# LEDATTACK.net
KiCad netlist of a schematic drawn in EAGLE
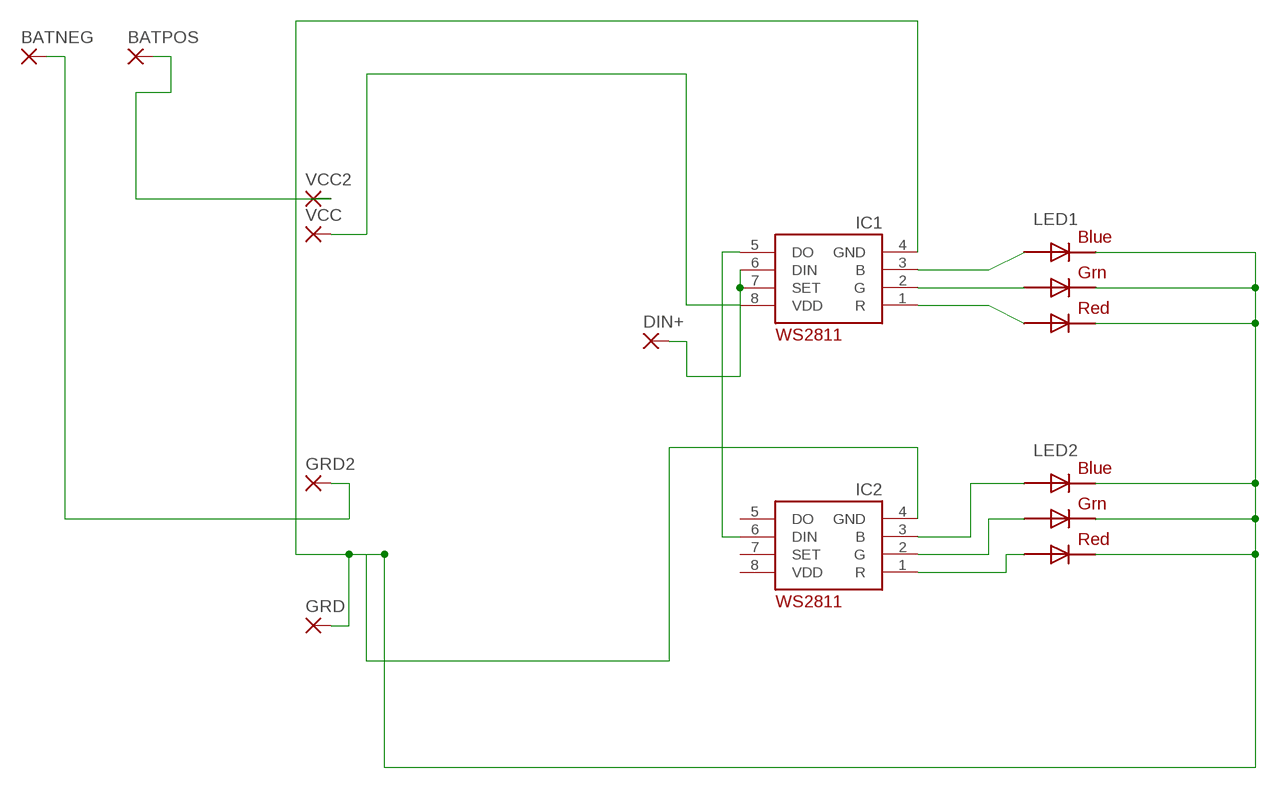
[diagram p0: schematic, sheet 1]

(export (version "E")
  (design (tool "Eeschema 10.0.6"))
  (components
    (comp (ref "BATNEG")
      (value "1,6/0,8")
      (footprint "eagle-import:1,6_0,8")
      (libsource (lib "eagle-import") (part "1,6/0,8"))
    )
    (comp (ref "BATPOS")
      (value "1,6/0,8")
      (footprint "eagle-import:1,6_0,8")
      (libsource (lib "eagle-import") (part "1,6/0,8"))
    )
    (comp (ref "DIN+")
      (value "1,6/0,8")
      (footprint "eagle-import:1,6_0,8")
      (libsource (lib "eagle-import") (part "1,6/0,8"))
    )
    (comp (ref "GRD")
      (value "1,6/0,8")
      (footprint "eagle-import:1,6_0,8")
      (libsource (lib "eagle-import") (part "1,6/0,8"))
    )
    (comp (ref "GRD2")
      (value "1,6/0,8")
      (footprint "eagle-import:1,6_0,8")
      (libsource (lib "eagle-import") (part "1,6/0,8"))
    )
    (comp (ref "IC1")
      (value "WS2811-SOP8")
      (footprint "eagle-import:SO08-SKINNYPADS")
      (libsource (lib "eagle-import") (part "WS2811-SOP8"))
    )
    (comp (ref "IC2")
      (value "WS2811-SOP8")
      (footprint "eagle-import:SO08-SKINNYPADS")
      (libsource (lib "eagle-import") (part "WS2811-SOP8"))
    )
    (comp (ref "LED1")
      (value "RGBLED5050")
      (footprint "eagle-import:RGBLED5050")
      (libsource (lib "eagle-import") (part "RGBLED5050"))
    )
    (comp (ref "LED2")
      (value "RGBLED5050")
      (footprint "eagle-import:RGBLED5050")
      (libsource (lib "eagle-import") (part "RGBLED5050"))
    )
    (comp (ref "VCC")
      (value "1,6/0,8")
      (footprint "eagle-import:1,6_0,8")
      (libsource (lib "eagle-import") (part "1,6/0,8"))
    )
    (comp (ref "VCC2")
      (value "1,6/0,8")
      (footprint "eagle-import:1,6_0,8")
      (libsource (lib "eagle-import") (part "1,6/0,8"))
    )
  )
  (nets
    (net (code "1") (name "/VDD") (class "Default")
      (node (ref "IC2") (pin "8") (pinfunction "VDD_8") (pintype "power_in"))
    )
    (net (code "2") (name "Net-(BATNEG-P)") (class "Default")
      (node (ref "BATNEG") (pin "1") (pinfunction "P_1") (pintype "passive"))
      (node (ref "GRD2") (pin "1") (pinfunction "P_1") (pintype "passive"))
    )
    (net (code "3") (name "Net-(BATPOS-P)") (class "Default")
      (node (ref "BATPOS") (pin "1") (pinfunction "P_1") (pintype "passive"))
      (node (ref "VCC2") (pin "1") (pinfunction "P_1") (pintype "passive"))
    )
    (net (code "4") (name "Net-(DIN+-P)") (class "Default")
      (node (ref "DIN+") (pin "1") (pinfunction "P_1") (pintype "passive"))
      (node (ref "IC1") (pin "6") (pinfunction "DIN_6") (pintype "input"))
      (node (ref "IC1") (pin "7") (pinfunction "SET_7") (pintype "input"))
    )
    (net (code "5") (name "Net-(GRD-P)") (class "Default")
      (node (ref "GRD") (pin "1") (pinfunction "P_1") (pintype "passive"))
      (node (ref "IC1") (pin "4") (pinfunction "GND_4") (pintype "power_in"))
      (node (ref "IC2") (pin "4") (pinfunction "GND_4") (pintype "power_in"))
      (node (ref "LED1") (pin "4") (pinfunction "BLUE_C_4") (pintype "bidirectional"))
      (node (ref "LED1") (pin "5") (pinfunction "RED_C_5") (pintype "bidirectional"))
      (node (ref "LED1") (pin "6") (pinfunction "GREEN_C_6") (pintype "bidirectional"))
      (node (ref "LED2") (pin "4") (pinfunction "BLUE_C_4") (pintype "bidirectional"))
      (node (ref "LED2") (pin "5") (pinfunction "RED_C_5") (pintype "bidirectional"))
      (node (ref "LED2") (pin "6") (pinfunction "GREEN_C_6") (pintype "bidirectional"))
    )
    (net (code "6") (name "Net-(IC1-B)") (class "Default")
      (node (ref "IC1") (pin "3") (pinfunction "B_3") (pintype "open_collector"))
      (node (ref "LED1") (pin "3") (pinfunction "BLUE_A_3") (pintype "bidirectional"))
    )
    (net (code "7") (name "Net-(IC1-DO)") (class "Default")
      (node (ref "IC1") (pin "5") (pinfunction "DO_5") (pintype "output"))
      (node (ref "IC2") (pin "6") (pinfunction "DIN_6") (pintype "input"))
    )
    (net (code "8") (name "Net-(IC1-G)") (class "Default")
      (node (ref "IC1") (pin "2") (pinfunction "G_2") (pintype "open_collector"))
      (node (ref "LED1") (pin "1") (pinfunction "GREEN_A_1") (pintype "bidirectional"))
    )
    (net (code "9") (name "Net-(IC1-R)") (class "Default")
      (node (ref "IC1") (pin "1") (pinfunction "R_1") (pintype "open_collector"))
      (node (ref "LED1") (pin "2") (pinfunction "RED_A_2") (pintype "bidirectional"))
    )
    (net (code "10") (name "Net-(IC1-VDD)") (class "Default")
      (node (ref "IC1") (pin "8") (pinfunction "VDD_8") (pintype "power_in"))
      (node (ref "VCC") (pin "1") (pinfunction "P_1") (pintype "passive"))
    )
    (net (code "11") (name "Net-(IC2-B)") (class "Default")
      (node (ref "IC2") (pin "3") (pinfunction "B_3") (pintype "open_collector"))
      (node (ref "LED2") (pin "3") (pinfunction "BLUE_A_3") (pintype "bidirectional"))
    )
    (net (code "12") (name "Net-(IC2-G)") (class "Default")
      (node (ref "IC2") (pin "2") (pinfunction "G_2") (pintype "open_collector"))
      (node (ref "LED2") (pin "1") (pinfunction "GREEN_A_1") (pintype "bidirectional"))
    )
    (net (code "13") (name "Net-(IC2-R)") (class "Default")
      (node (ref "IC2") (pin "1") (pinfunction "R_1") (pintype "open_collector"))
      (node (ref "LED2") (pin "2") (pinfunction "RED_A_2") (pintype "bidirectional"))
    )
    (net (code "14") (name "unconnected-(IC2-DO-Pad5)") (class "Default")
      (node (ref "IC2") (pin "5") (pinfunction "DO_5") (pintype "output"))
    )
    (net (code "15") (name "unconnected-(IC2-SET-Pad7)") (class "Default")
      (node (ref "IC2") (pin "7") (pinfunction "SET_7") (pintype "input"))
    )
  )
)
